# Sheet6.net
KiCad netlist of a schematic drawn in Altium Designer
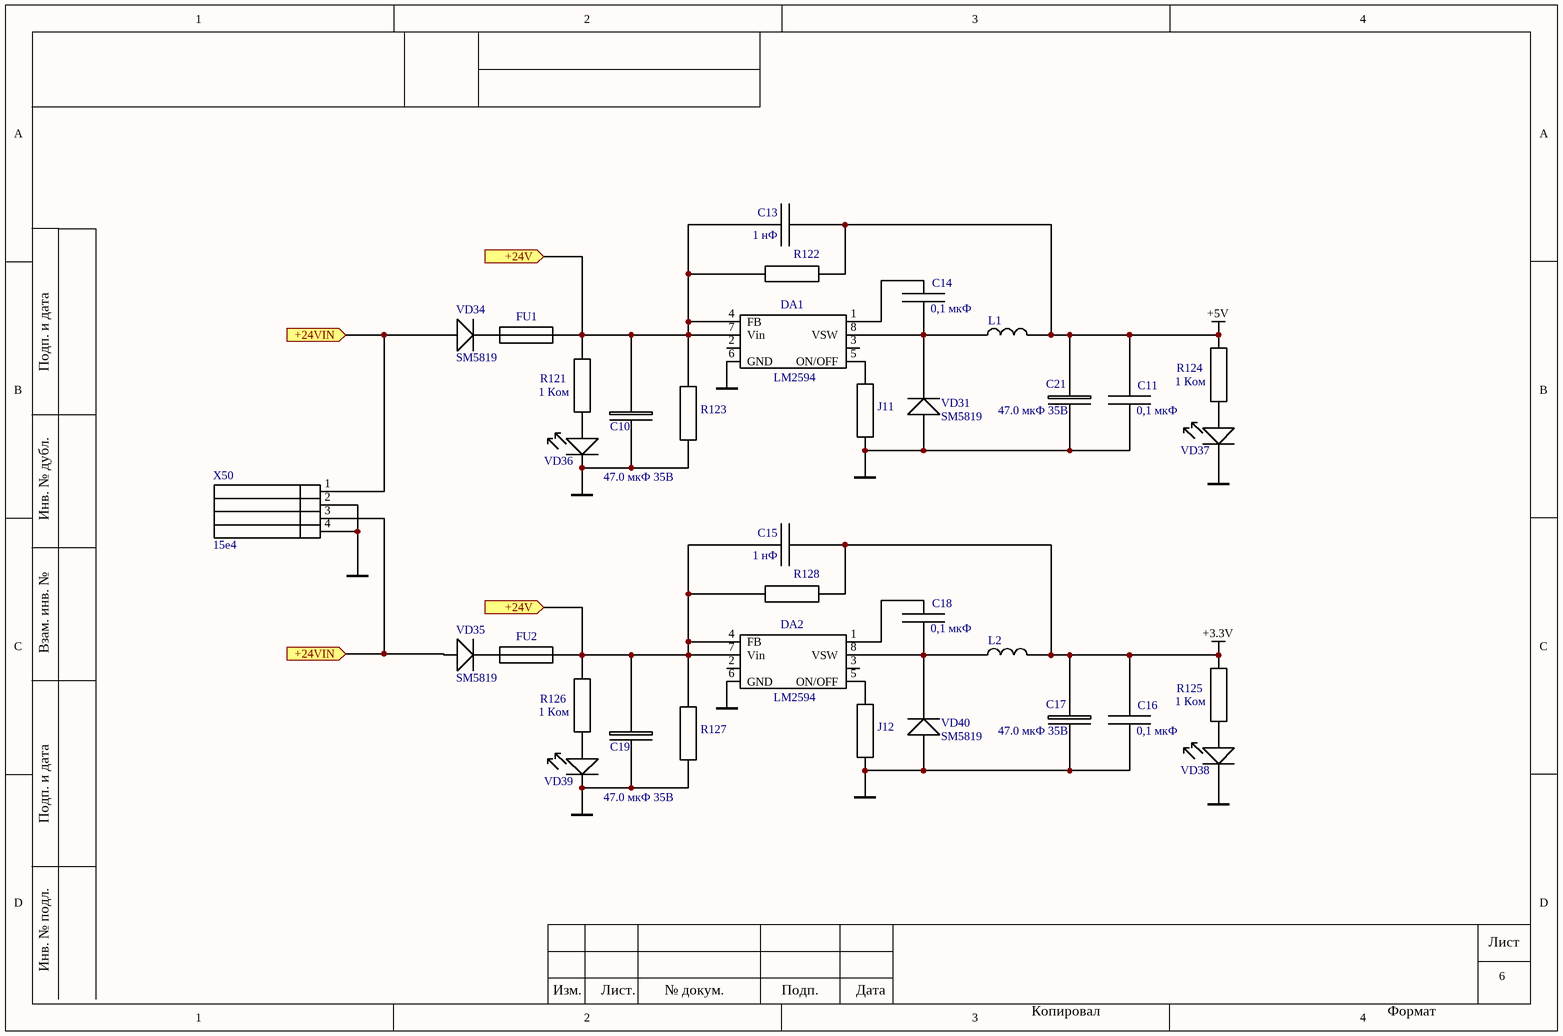
[diagram p0: Sheet6.SchDoc]

(export (version "E")
  (design (tool "Eeschema 10.0.6"))
  (components
    (comp (ref "C10")
      (value "C_e")
      (fields (field (name "ALTIUM_UNNAMED_1") "47.0 мкФ 35В"))
      (libsource (lib "Board_QFP") (part "C_e"))
    )
    (comp (ref "C11")
      (value "C0805")
      (fields (field (name "ALTIUM_UNNAMED_1") "0,1 мкФ"))
      (libsource (lib "Board_QFP") (part "C0805"))
    )
    (comp (ref "C13")
      (value "C0805")
      (fields (field (name "ALTIUM_UNNAMED_1") "1 нФ"))
      (libsource (lib "Board_QFP") (part "C0805"))
    )
    (comp (ref "C14")
      (value "C0805")
      (fields (field (name "ALTIUM_UNNAMED_1") "0,1 мкФ"))
      (libsource (lib "Board_QFP") (part "C0805"))
    )
    (comp (ref "C15")
      (value "C0805")
      (fields (field (name "ALTIUM_UNNAMED_1") "1 нФ"))
      (libsource (lib "Board_QFP") (part "C0805"))
    )
    (comp (ref "C16")
      (value "C0805")
      (fields (field (name "ALTIUM_UNNAMED_1") "0,1 мкФ"))
      (libsource (lib "Board_QFP") (part "C0805"))
    )
    (comp (ref "C17")
      (value "C_e")
      (fields (field (name "ALTIUM_UNNAMED_1") "47.0 мкФ 35В"))
      (libsource (lib "Board_QFP") (part "C_e"))
    )
    (comp (ref "C18")
      (value "C0805")
      (fields (field (name "ALTIUM_UNNAMED_1") "0,1 мкФ"))
      (libsource (lib "Board_QFP") (part "C0805"))
    )
    (comp (ref "C19")
      (value "C_e")
      (fields (field (name "ALTIUM_UNNAMED_1") "47.0 мкФ 35В"))
      (libsource (lib "Board_QFP") (part "C_e"))
    )
    (comp (ref "C21")
      (value "C_e")
      (fields (field (name "ALTIUM_UNNAMED_1") "47.0 мкФ 35В"))
      (libsource (lib "Board_QFP") (part "C_e"))
    )
    (comp (ref "DA1") (value "LM2594") (libsource (lib "Board_QFP") (part "LM2594")))
    (comp (ref "DA2") (value "LM2594") (libsource (lib "Board_QFP") (part "LM2594")))
    (comp (ref "FU1") (value "FU") (libsource (lib "Board_QFP") (part "FU")))
    (comp (ref "FU2") (value "FU") (libsource (lib "Board_QFP") (part "FU")))
    (comp (ref "J11") (value "R0805") (libsource (lib "Board_QFP") (part "R0805")))
    (comp (ref "J12") (value "R0805") (libsource (lib "Board_QFP") (part "R0805")))
    (comp (ref "L1") (value "DR") (libsource (lib "Board_QFP") (part "DR")))
    (comp (ref "L2") (value "DR") (libsource (lib "Board_QFP") (part "DR")))
    (comp (ref "R121")
      (value "R0805")
      (fields (field (name "ALTIUM_UNNAMED_1") "1 Ком"))
      (libsource (lib "Board_QFP") (part "R0805"))
    )
    (comp (ref "R122") (value "R0805") (libsource (lib "Board_QFP") (part "R0805")))
    (comp (ref "R123") (value "R0805") (libsource (lib "Board_QFP") (part "R0805")))
    (comp (ref "R124")
      (value "R0805")
      (fields (field (name "ALTIUM_UNNAMED_1") "1 Ком"))
      (libsource (lib "Board_QFP") (part "R0805"))
    )
    (comp (ref "R125")
      (value "R0805")
      (fields (field (name "ALTIUM_UNNAMED_1") "1 Ком"))
      (libsource (lib "Board_QFP") (part "R0805"))
    )
    (comp (ref "R126")
      (value "R0805")
      (fields (field (name "ALTIUM_UNNAMED_1") "1 Ком"))
      (libsource (lib "Board_QFP") (part "R0805"))
    )
    (comp (ref "R127") (value "R0805") (libsource (lib "Board_QFP") (part "R0805")))
    (comp (ref "R128") (value "R0805") (libsource (lib "Board_QFP") (part "R0805")))
    (comp (ref "VD31") (value "SM5819") (libsource (lib "Board_QFP") (part "Diod")))
    (comp (ref "VD34") (value "SM5819") (libsource (lib "Board_QFP") (part "Diod")))
    (comp (ref "VD35") (value "SM5819") (libsource (lib "Board_QFP") (part "Diod")))
    (comp (ref "VD36") (value "LED") (libsource (lib "Board_QFP") (part "LED")))
    (comp (ref "VD37") (value "LED") (libsource (lib "Board_QFP") (part "LED")))
    (comp (ref "VD38") (value "LED") (libsource (lib "Board_QFP") (part "LED")))
    (comp (ref "VD39") (value "LED") (libsource (lib "Board_QFP") (part "LED")))
    (comp (ref "VD40") (value "SM5819") (libsource (lib "Board_QFP") (part "Diod")))
    (comp (ref "X50") (value "15e4") (libsource (lib "Board_QFP") (part "15e4")))
  )
  (nets
    (net (code "1") (name "+3.3V") (class "Default")
      (node (ref "C15") (pin "2") (pinfunction "2_2") (pintype "passive"))
      (node (ref "C16") (pin "2") (pinfunction "2_2") (pintype "passive"))
      (node (ref "C17") (pin "1") (pinfunction "1_1") (pintype "passive"))
      (node (ref "L2") (pin "2") (pinfunction "2_2") (pintype "passive"))
      (node (ref "R125") (pin "1") (pinfunction "1_1") (pintype "passive"))
      (node (ref "R128") (pin "2") (pinfunction "2_2") (pintype "passive"))
    )
    (net (code "2") (name "+5V") (class "Default")
      (node (ref "C11") (pin "2") (pinfunction "2_2") (pintype "passive"))
      (node (ref "C13") (pin "2") (pinfunction "2_2") (pintype "passive"))
      (node (ref "C21") (pin "1") (pinfunction "1_1") (pintype "passive"))
      (node (ref "L1") (pin "2") (pinfunction "2_2") (pintype "passive"))
      (node (ref "R122") (pin "2") (pinfunction "2_2") (pintype "passive"))
      (node (ref "R124") (pin "1") (pinfunction "1_1") (pintype "passive"))
    )
    (net (code "3") (name "/+24V") (class "Default")
      (node (ref "C10") (pin "1") (pinfunction "1_1") (pintype "passive"))
      (node (ref "C13") (pin "1") (pinfunction "1_1") (pintype "passive"))
      (node (ref "C15") (pin "1") (pinfunction "1_1") (pintype "passive"))
      (node (ref "C19") (pin "1") (pinfunction "1_1") (pintype "passive"))
      (node (ref "DA1") (pin "4") (pinfunction "FB_4") (pintype "passive"))
      (node (ref "DA1") (pin "7") (pinfunction "Vin_7") (pintype "passive"))
      (node (ref "DA2") (pin "4") (pinfunction "FB_4") (pintype "passive"))
      (node (ref "DA2") (pin "7") (pinfunction "Vin_7") (pintype "passive"))
      (node (ref "FU1") (pin "2") (pinfunction "2_2") (pintype "passive"))
      (node (ref "FU2") (pin "2") (pinfunction "2_2") (pintype "passive"))
      (node (ref "R121") (pin "1") (pinfunction "1_1") (pintype "passive"))
      (node (ref "R122") (pin "1") (pinfunction "1_1") (pintype "passive"))
      (node (ref "R123") (pin "1") (pinfunction "1_1") (pintype "passive"))
      (node (ref "R126") (pin "1") (pinfunction "1_1") (pintype "passive"))
      (node (ref "R127") (pin "1") (pinfunction "1_1") (pintype "passive"))
      (node (ref "R128") (pin "1") (pinfunction "1_1") (pintype "passive"))
    )
    (net (code "4") (name "/+24VIN") (class "Default")
      (node (ref "VD34") (pin "2") (pinfunction "K_2") (pintype "passive"))
      (node (ref "VD35") (pin "2") (pinfunction "K_2") (pintype "passive"))
      (node (ref "X50") (pin "1") (pinfunction "1_1") (pintype "passive"))
      (node (ref "X50") (pin "3") (pinfunction "3_3") (pintype "passive"))
    )
    (net (code "5") (name "GND") (class "Default")
      (node (ref "C10") (pin "2") (pinfunction "2_2") (pintype "passive"))
      (node (ref "C11") (pin "1") (pinfunction "1_1") (pintype "passive"))
      (node (ref "C16") (pin "1") (pinfunction "1_1") (pintype "passive"))
      (node (ref "C17") (pin "2") (pinfunction "2_2") (pintype "passive"))
      (node (ref "C19") (pin "2") (pinfunction "2_2") (pintype "passive"))
      (node (ref "C21") (pin "2") (pinfunction "2_2") (pintype "passive"))
      (node (ref "DA1") (pin "6") (pinfunction "GND_6") (pintype "passive"))
      (node (ref "DA2") (pin "6") (pinfunction "GND_6") (pintype "passive"))
      (node (ref "J11") (pin "2") (pinfunction "2_2") (pintype "passive"))
      (node (ref "J12") (pin "2") (pinfunction "2_2") (pintype "passive"))
      (node (ref "R123") (pin "2") (pinfunction "2_2") (pintype "passive"))
      (node (ref "R127") (pin "2") (pinfunction "2_2") (pintype "passive"))
      (node (ref "VD31") (pin "2") (pinfunction "K_2") (pintype "passive"))
      (node (ref "VD36") (pin "1") (pinfunction "A_1") (pintype "passive"))
      (node (ref "VD37") (pin "1") (pinfunction "A_1") (pintype "passive"))
      (node (ref "VD38") (pin "1") (pinfunction "A_1") (pintype "passive"))
      (node (ref "VD39") (pin "1") (pinfunction "A_1") (pintype "passive"))
      (node (ref "VD40") (pin "2") (pinfunction "K_2") (pintype "passive"))
      (node (ref "X50") (pin "2") (pinfunction "2_2") (pintype "passive"))
      (node (ref "X50") (pin "4") (pinfunction "4_4") (pintype "passive"))
    )
    (net (code "6") (name "Net-(DA1-CB)") (class "Default")
      (node (ref "C14") (pin "2") (pinfunction "2_2") (pintype "passive"))
      (node (ref "DA1") (pin "1") (pinfunction "CB_1") (pintype "passive"))
    )
    (net (code "7") (name "Net-(DA1-ON{slash}OFF)") (class "Default")
      (node (ref "DA1") (pin "5") (pinfunction "ON/OFF_5") (pintype "passive"))
      (node (ref "J11") (pin "1") (pinfunction "1_1") (pintype "passive"))
    )
    (net (code "8") (name "Net-(DA1-VSW)") (class "Default")
      (node (ref "C14") (pin "1") (pinfunction "1_1") (pintype "passive"))
      (node (ref "DA1") (pin "8") (pinfunction "VSW_8") (pintype "passive"))
      (node (ref "L1") (pin "1") (pinfunction "1_1") (pintype "passive"))
      (node (ref "VD31") (pin "1") (pinfunction "A_1") (pintype "passive"))
    )
    (net (code "9") (name "Net-(DA2-CB)") (class "Default")
      (node (ref "C18") (pin "2") (pinfunction "2_2") (pintype "passive"))
      (node (ref "DA2") (pin "1") (pinfunction "CB_1") (pintype "passive"))
    )
    (net (code "10") (name "Net-(DA2-ON{slash}OFF)") (class "Default")
      (node (ref "DA2") (pin "5") (pinfunction "ON/OFF_5") (pintype "passive"))
      (node (ref "J12") (pin "1") (pinfunction "1_1") (pintype "passive"))
    )
    (net (code "11") (name "Net-(DA2-VSW)") (class "Default")
      (node (ref "C18") (pin "1") (pinfunction "1_1") (pintype "passive"))
      (node (ref "DA2") (pin "8") (pinfunction "VSW_8") (pintype "passive"))
      (node (ref "L2") (pin "1") (pinfunction "1_1") (pintype "passive"))
      (node (ref "VD40") (pin "1") (pinfunction "A_1") (pintype "passive"))
    )
    (net (code "12") (name "Net-(VD34-A)") (class "Default")
      (node (ref "FU1") (pin "1") (pinfunction "1_1") (pintype "passive"))
      (node (ref "VD34") (pin "1") (pinfunction "A_1") (pintype "passive"))
    )
    (net (code "13") (name "Net-(VD35-A)") (class "Default")
      (node (ref "FU2") (pin "1") (pinfunction "1_1") (pintype "passive"))
      (node (ref "VD35") (pin "1") (pinfunction "A_1") (pintype "passive"))
    )
    (net (code "14") (name "Net-(VD36-K)") (class "Default")
      (node (ref "R121") (pin "2") (pinfunction "2_2") (pintype "passive"))
      (node (ref "VD36") (pin "2") (pinfunction "K_2") (pintype "passive"))
    )
    (net (code "15") (name "Net-(VD37-K)") (class "Default")
      (node (ref "R124") (pin "2") (pinfunction "2_2") (pintype "passive"))
      (node (ref "VD37") (pin "2") (pinfunction "K_2") (pintype "passive"))
    )
    (net (code "16") (name "Net-(VD38-K)") (class "Default")
      (node (ref "R125") (pin "2") (pinfunction "2_2") (pintype "passive"))
      (node (ref "VD38") (pin "2") (pinfunction "K_2") (pintype "passive"))
    )
    (net (code "17") (name "Net-(VD39-K)") (class "Default")
      (node (ref "R126") (pin "2") (pinfunction "2_2") (pintype "passive"))
      (node (ref "VD39") (pin "2") (pinfunction "K_2") (pintype "passive"))
    )
    (net (code "18") (name "unconnected-(DA1-Pad2)") (class "Default")
      (node (ref "DA1") (pin "2") (pinfunction "2_2") (pintype "passive"))
    )
    (net (code "19") (name "unconnected-(DA1-Pad3)") (class "Default")
      (node (ref "DA1") (pin "3") (pinfunction "3_3") (pintype "passive"))
    )
    (net (code "20") (name "unconnected-(DA2-Pad2)") (class "Default")
      (node (ref "DA2") (pin "2") (pinfunction "2_2") (pintype "passive"))
    )
    (net (code "21") (name "unconnected-(DA2-Pad3)") (class "Default")
      (node (ref "DA2") (pin "3") (pinfunction "3_3") (pintype "passive"))
    )
  )
)
